# 1554E.net
KiCad netlist of a schematic drawn in EAGLE
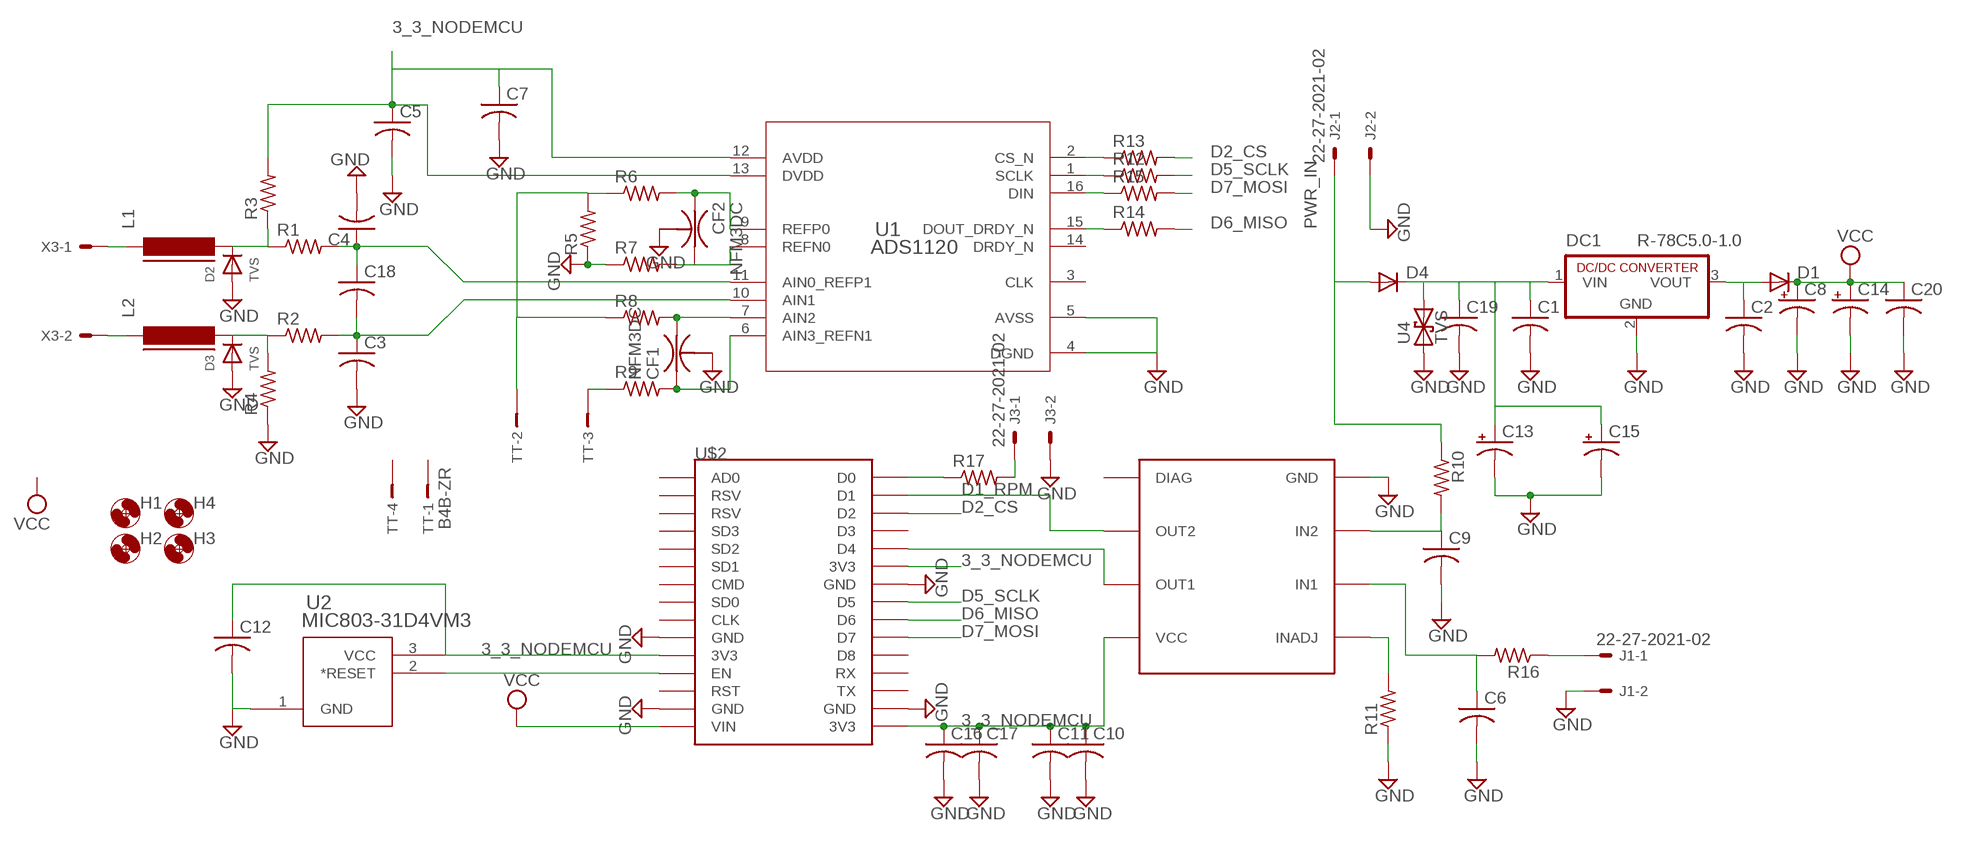
[diagram p0: schematic, sheet 1]

(export (version "E")
  (design (tool "Eeschema 10.0.6"))
  (components
    (comp (ref "C1")
      (value "C-USC0805K")
      (footprint "eagle-import:C0805K")
      (libsource (lib "eagle-import") (part "C-USC0805K"))
    )
    (comp (ref "C2")
      (value "C-USC0805K")
      (footprint "eagle-import:C0805K")
      (libsource (lib "eagle-import") (part "C-USC0805K"))
    )
    (comp (ref "C3")
      (value "C-USC0805K")
      (footprint "eagle-import:C0805K")
      (libsource (lib "eagle-import") (part "C-USC0805K"))
    )
    (comp (ref "C4")
      (value "C-USC0805K")
      (footprint "eagle-import:C0805K")
      (libsource (lib "eagle-import") (part "C-USC0805K"))
    )
    (comp (ref "C5")
      (value "C-USC0805K")
      (footprint "eagle-import:C0805K")
      (libsource (lib "eagle-import") (part "C-USC0805K"))
    )
    (comp (ref "C6")
      (value "C-USC0805K")
      (footprint "eagle-import:C0805K")
      (libsource (lib "eagle-import") (part "C-USC0805K"))
    )
    (comp (ref "C7")
      (value "C-USC0805K")
      (footprint "eagle-import:C0805K")
      (libsource (lib "eagle-import") (part "C-USC0805K"))
    )
    (comp (ref "C8")
      (value "CPOL-USE2.5-5")
      (footprint "eagle-import:E2,5-5")
      (libsource (lib "eagle-import") (part "CPOL-USE2.5-5"))
    )
    (comp (ref "C9")
      (value "C-USC0805K")
      (footprint "eagle-import:C0805K")
      (libsource (lib "eagle-import") (part "C-USC0805K"))
    )
    (comp (ref "C10")
      (value "C-USC0805K")
      (footprint "eagle-import:C0805K")
      (libsource (lib "eagle-import") (part "C-USC0805K"))
    )
    (comp (ref "C11")
      (value "C-USC0805K")
      (footprint "eagle-import:C0805K")
      (libsource (lib "eagle-import") (part "C-USC0805K"))
    )
    (comp (ref "C12")
      (value "C-USC0805K")
      (footprint "eagle-import:C0805K")
      (libsource (lib "eagle-import") (part "C-USC0805K"))
    )
    (comp (ref "C13")
      (value "CPOL-USE2.5-5")
      (footprint "eagle-import:E2,5-5")
      (libsource (lib "eagle-import") (part "CPOL-USE2.5-5"))
    )
    (comp (ref "C14")
      (value "CPOL-USE2.5-5")
      (footprint "eagle-import:E2,5-5")
      (libsource (lib "eagle-import") (part "CPOL-USE2.5-5"))
    )
    (comp (ref "C15")
      (value "CPOL-USE7.5-16")
      (footprint "eagle-import:E7,5-16")
      (libsource (lib "eagle-import") (part "CPOL-USE7.5-16"))
    )
    (comp (ref "C16")
      (value "C-USC1206K")
      (footprint "eagle-import:C1206K")
      (libsource (lib "eagle-import") (part "C-USC1206K"))
    )
    (comp (ref "C17")
      (value "C-USC1206K")
      (footprint "eagle-import:C1206K")
      (libsource (lib "eagle-import") (part "C-USC1206K"))
    )
    (comp (ref "C18")
      (value "C-USC0805K")
      (footprint "eagle-import:C0805K")
      (libsource (lib "eagle-import") (part "C-USC0805K"))
    )
    (comp (ref "C19")
      (value "C-USC1206K")
      (footprint "eagle-import:C1206K")
      (libsource (lib "eagle-import") (part "C-USC1206K"))
    )
    (comp (ref "C20")
      (value "C-USC1206K")
      (footprint "eagle-import:C1206K")
      (libsource (lib "eagle-import") (part "C-USC1206K"))
    )
    (comp (ref "CF1")
      (value "NFM3DC")
      (footprint "eagle-import:NFM3DC")
      (fields (field (name "MF") "FARNELL") (field (name "MPN") "NFM3DCC470U1H3L"))
      (libsource (lib "eagle-import") (part "NFM3DC"))
    )
    (comp (ref "CF2")
      (value "NFM3DC")
      (footprint "eagle-import:NFM3DC")
      (fields (field (name "MF") "FARNELL") (field (name "MPN") "NFM3DCC470U1H3L"))
      (libsource (lib "eagle-import") (part "NFM3DC"))
    )
    (comp (ref "D1")
      (value "DIODE-DO-214AC")
      (footprint "eagle-import:DO-214AC")
      (libsource (lib "eagle-import") (part "DIODE-DO-214AC"))
    )
    (comp (ref "D2")
      (value "TVS")
      (footprint "eagle-import:SOD-323F")
      (libsource (lib "eagle-import") (part "DIODESOD-323F"))
    )
    (comp (ref "D3")
      (value "TVS")
      (footprint "eagle-import:SOD-323F")
      (libsource (lib "eagle-import") (part "DIODESOD-323F"))
    )
    (comp (ref "D4")
      (value "DIODE-DO-214AC")
      (footprint "eagle-import:DO-214AC")
      (libsource (lib "eagle-import") (part "DIODE-DO-214AC"))
    )
    (comp (ref "DC1")
      (value "R-78C5.0-1.0")
      (footprint "eagle-import:SIP3")
      (libsource (lib "eagle-import") (part "R-78C-1.05.0"))
    )
    (comp (ref "H1")
      (value "MOUNT-HOLE2.8")
      (footprint "eagle-import:2,8")
      (libsource (lib "eagle-import") (part "MOUNT-HOLE2.8"))
    )
    (comp (ref "H2")
      (value "MOUNT-HOLE2.8")
      (footprint "eagle-import:2,8")
      (libsource (lib "eagle-import") (part "MOUNT-HOLE2.8"))
    )
    (comp (ref "H3")
      (value "MOUNT-HOLE2.8")
      (footprint "eagle-import:2,8")
      (libsource (lib "eagle-import") (part "MOUNT-HOLE2.8"))
    )
    (comp (ref "H4")
      (value "MOUNT-HOLE2.8")
      (footprint "eagle-import:2,8")
      (libsource (lib "eagle-import") (part "MOUNT-HOLE2.8"))
    )
    (comp (ref "J1")
      (value "22-27-2021-02")
      (footprint "eagle-import:6410-02")
      (libsource (lib "eagle-import") (part "22-?-0227-2021"))
    )
    (comp (ref "J2")
      (value "22-27-2021-02")
      (footprint "eagle-import:6410-02")
      (libsource (lib "eagle-import") (part "22-?-0227-2021"))
    )
    (comp (ref "J3")
      (value "22-27-2021-02")
      (footprint "eagle-import:6410-02")
      (libsource (lib "eagle-import") (part "22-?-0227-2021"))
    )
    (comp (ref "L1")
      (value "FERRITE-0805")
      (footprint "eagle-import:FB805")
      (libsource (lib "eagle-import") (part "FERRITE-0805"))
    )
    (comp (ref "L2")
      (value "FERRITE-0805")
      (footprint "eagle-import:FB805")
      (libsource (lib "eagle-import") (part "FERRITE-0805"))
    )
    (comp (ref "R1")
      (value "R-US_R0805W")
      (footprint "eagle-import:R0805W")
      (libsource (lib "eagle-import") (part "R-US_R0805W"))
    )
    (comp (ref "R2")
      (value "R-US_R0805W")
      (footprint "eagle-import:R0805W")
      (libsource (lib "eagle-import") (part "R-US_R0805W"))
    )
    (comp (ref "R3")
      (value "R-US_R0805W")
      (footprint "eagle-import:R0805W")
      (libsource (lib "eagle-import") (part "R-US_R0805W"))
    )
    (comp (ref "R4")
      (value "R-US_R0805W")
      (footprint "eagle-import:R0805W")
      (libsource (lib "eagle-import") (part "R-US_R0805W"))
    )
    (comp (ref "R5")
      (value "R-US_R0805W")
      (footprint "eagle-import:R0805W")
      (libsource (lib "eagle-import") (part "R-US_R0805W"))
    )
    (comp (ref "R6")
      (value "R-US_R0805W")
      (footprint "eagle-import:R0805W")
      (libsource (lib "eagle-import") (part "R-US_R0805W"))
    )
    (comp (ref "R7")
      (value "R-US_R0805W")
      (footprint "eagle-import:R0805W")
      (libsource (lib "eagle-import") (part "R-US_R0805W"))
    )
    (comp (ref "R8")
      (value "R-US_R0805W")
      (footprint "eagle-import:R0805W")
      (libsource (lib "eagle-import") (part "R-US_R0805W"))
    )
    (comp (ref "R9")
      (value "R-US_R0805W")
      (footprint "eagle-import:R0805W")
      (libsource (lib "eagle-import") (part "R-US_R0805W"))
    )
    (comp (ref "R10")
      (value "R-US_R0805W")
      (footprint "eagle-import:R0805W")
      (libsource (lib "eagle-import") (part "R-US_R0805W"))
    )
    (comp (ref "R11")
      (value "R-US_R0805W")
      (footprint "eagle-import:R0805W")
      (libsource (lib "eagle-import") (part "R-US_R0805W"))
    )
    (comp (ref "R12")
      (value "R-US_R0805W")
      (footprint "eagle-import:R0805W")
      (libsource (lib "eagle-import") (part "R-US_R0805W"))
    )
    (comp (ref "R13")
      (value "R-US_R0805W")
      (footprint "eagle-import:R0805W")
      (libsource (lib "eagle-import") (part "R-US_R0805W"))
    )
    (comp (ref "R14")
      (value "R-US_R0805W")
      (footprint "eagle-import:R0805W")
      (libsource (lib "eagle-import") (part "R-US_R0805W"))
    )
    (comp (ref "R15")
      (value "R-US_R0805W")
      (footprint "eagle-import:R0805W")
      (libsource (lib "eagle-import") (part "R-US_R0805W"))
    )
    (comp (ref "R16")
      (value "R-US_R0805W")
      (footprint "eagle-import:R0805W")
      (libsource (lib "eagle-import") (part "R-US_R0805W"))
    )
    (comp (ref "R17")
      (value "R-US_R0805W")
      (footprint "eagle-import:R0805W")
      (libsource (lib "eagle-import") (part "R-US_R0805W"))
    )
    (comp (ref "TT")
      (value "B4B-ZR")
      (footprint "eagle-import:B4B-ZR")
      (fields (field (name "MF") "FARNELL") (field (name "MPN") "B4B-ZR(LF)(SN)"))
      (libsource (lib "eagle-import") (part "?4B-ZRB"))
    )
    (comp (ref "U$1")
      (value "NCV1124")
      (footprint "eagle-import:TESTER")
      (libsource (lib "eagle-import") (part "NCV1124"))
    )
    (comp (ref "U$2")
      (value "ESP12E_DEVKIT")
      (footprint "eagle-import:ESP12E_DEVKIT")
      (libsource (lib "eagle-import") (part "ESP12E_DEVKIT"))
    )
    (comp (ref "U1")
      (value "ADS1120")
      (footprint "eagle-import:PW0016A_N")
      (fields
        (field (name "ALTERNATEPARTNUMBER") "ADS1120IPW")
        (field (name "MANUFACTURER") "Texas Instruments")
        (field (name "PARTNUMBER") "ADS1120IPWR")
      )
      (libsource (lib "eagle-import") (part "ADS1120IPWR"))
    )
    (comp (ref "U2")
      (value "MIC803-31D4VM3")
      (footprint "eagle-import:SOT-23_M3")
      (fields
        (field (name "MANUFACTURER_PART_NUMBER") "mic803-31d4vm3")
        (field (name "COPYRIGHT") "Copyright (C) 2015 Accelerated Designs. All rights reserved")
      )
      (libsource (lib "eagle-import") (part "MIC803-31D4VM3"))
    )
    (comp (ref "U4")
      (value "TVS")
      (footprint "eagle-import:SMA-DIODE")
      (libsource (lib "eagle-import") (part "TVS"))
    )
    (comp (ref "X3")
      (value "22-23-2021")
      (footprint "eagle-import:22-23-2021")
      (fields
        (field (name "MF") "MOLEX")
        (field (name "MF_1") "MOLEX")
        (field (name "MPN") "22-23-2021")
        (field (name "OC_FARNELL") "1462926")
        (field (name "OC_NEWARK") "25C3832")
      )
      (libsource (lib "eagle-import") (part "22-23-2021"))
    )
  )
  (nets
    (net (code "1") (name "/3_3_NODEMCU") (class "Default")
      (node (ref "C10") (pin "1") (pinfunction "1_1") (pintype "passive"))
      (node (ref "C11") (pin "1") (pinfunction "1_1") (pintype "passive"))
      (node (ref "C12") (pin "1") (pinfunction "1_1") (pintype "passive"))
      (node (ref "C16") (pin "1") (pinfunction "1_1") (pintype "passive"))
      (node (ref "C17") (pin "1") (pinfunction "1_1") (pintype "passive"))
      (node (ref "C5") (pin "1") (pinfunction "1_1") (pintype "passive"))
      (node (ref "C7") (pin "1") (pinfunction "1_1") (pintype "passive"))
      (node (ref "R3") (pin "2") (pinfunction "2_2") (pintype "passive"))
      (node (ref "U$1") (pin "VCC") (pinfunction "VCC_VCC") (pintype "bidirectional"))
      (node (ref "U$2") (pin "3V3@0") (pinfunction "3V3_3V3@0") (pintype "bidirectional"))
      (node (ref "U$2") (pin "3V3@1") (pinfunction "3V3_3V3@1") (pintype "bidirectional"))
      (node (ref "U$2") (pin "3V3@2") (pinfunction "3V3_3V3@2") (pintype "bidirectional"))
      (node (ref "U1") (pin "12") (pinfunction "AVDD_12") (pintype "power_in"))
      (node (ref "U1") (pin "13") (pinfunction "DVDD_13") (pintype "power_in"))
      (node (ref "U2") (pin "3") (pinfunction "VCC_3") (pintype "power_in"))
    )
    (net (code "2") (name "/D1_RPM") (class "Default")
      (node (ref "U$1") (pin "OUT2") (pinfunction "OUT2_OUT2") (pintype "bidirectional"))
      (node (ref "U$2") (pin "D1") (pinfunction "D1_D1") (pintype "bidirectional"))
    )
    (net (code "3") (name "/D2_CS") (class "Default")
      (node (ref "R13") (pin "2") (pinfunction "2_2") (pintype "passive"))
      (node (ref "U$2") (pin "D2") (pinfunction "D2_D2") (pintype "bidirectional"))
    )
    (net (code "4") (name "/D5_SCLK") (class "Default")
      (node (ref "R12") (pin "2") (pinfunction "2_2") (pintype "passive"))
      (node (ref "U$2") (pin "D5") (pinfunction "D5_D5") (pintype "bidirectional"))
    )
    (net (code "5") (name "/D6_MISO") (class "Default")
      (node (ref "R14") (pin "2") (pinfunction "2_2") (pintype "passive"))
      (node (ref "U$2") (pin "D6") (pinfunction "D6_D6") (pintype "bidirectional"))
    )
    (net (code "6") (name "/D7_MOSI") (class "Default")
      (node (ref "R15") (pin "2") (pinfunction "2_2") (pintype "passive"))
      (node (ref "U$2") (pin "D7") (pinfunction "D7_D7") (pintype "bidirectional"))
    )
    (net (code "7") (name "/PWR_IN") (class "Default")
      (node (ref "D4") (pin "A") (pinfunction "A_A") (pintype "passive"))
      (node (ref "J2") (pin "1") (pinfunction "S_1") (pintype "passive"))
      (node (ref "R10") (pin "1") (pinfunction "1_1") (pintype "passive"))
    )
    (net (code "8") (name "GND") (class "Default")
      (node (ref "C1") (pin "2") (pinfunction "2_2") (pintype "passive"))
      (node (ref "C10") (pin "2") (pinfunction "2_2") (pintype "passive"))
      (node (ref "C11") (pin "2") (pinfunction "2_2") (pintype "passive"))
      (node (ref "C12") (pin "2") (pinfunction "2_2") (pintype "passive"))
      (node (ref "C13") (pin "-") (pinfunction "-_-") (pintype "passive"))
      (node (ref "C14") (pin "-") (pinfunction "-_-") (pintype "passive"))
      (node (ref "C15") (pin "-") (pinfunction "-_-") (pintype "passive"))
      (node (ref "C16") (pin "2") (pinfunction "2_2") (pintype "passive"))
      (node (ref "C17") (pin "2") (pinfunction "2_2") (pintype "passive"))
      (node (ref "C19") (pin "2") (pinfunction "2_2") (pintype "passive"))
      (node (ref "C2") (pin "2") (pinfunction "2_2") (pintype "passive"))
      (node (ref "C20") (pin "2") (pinfunction "2_2") (pintype "passive"))
      (node (ref "C3") (pin "2") (pinfunction "2_2") (pintype "passive"))
      (node (ref "C4") (pin "2") (pinfunction "2_2") (pintype "passive"))
      (node (ref "C5") (pin "2") (pinfunction "2_2") (pintype "passive"))
      (node (ref "C6") (pin "2") (pinfunction "2_2") (pintype "passive"))
      (node (ref "C7") (pin "2") (pinfunction "2_2") (pintype "passive"))
      (node (ref "C8") (pin "-") (pinfunction "-_-") (pintype "passive"))
      (node (ref "C9") (pin "2") (pinfunction "2_2") (pintype "passive"))
      (node (ref "CF1") (pin "2@1") (pinfunction "2_2@1") (pintype "passive"))
      (node (ref "CF2") (pin "2@1") (pinfunction "2_2@1") (pintype "passive"))
      (node (ref "D2") (pin "A") (pinfunction "A_A") (pintype "passive"))
      (node (ref "D3") (pin "A") (pinfunction "A_A") (pintype "passive"))
      (node (ref "DC1") (pin "2") (pinfunction "GND_2") (pintype "passive"))
      (node (ref "J1") (pin "2") (pinfunction "S_2") (pintype "passive"))
      (node (ref "J2") (pin "2") (pinfunction "S_2") (pintype "passive"))
      (node (ref "J3") (pin "2") (pinfunction "S_2") (pintype "passive"))
      (node (ref "R11") (pin "1") (pinfunction "1_1") (pintype "passive"))
      (node (ref "R4") (pin "1") (pinfunction "1_1") (pintype "passive"))
      (node (ref "R5") (pin "1") (pinfunction "1_1") (pintype "passive"))
      (node (ref "R7") (pin "1") (pinfunction "1_1") (pintype "passive"))
      (node (ref "U$1") (pin "GND") (pinfunction "GND_GND") (pintype "bidirectional"))
      (node (ref "U$2") (pin "GND@0") (pinfunction "GND_GND@0") (pintype "bidirectional"))
      (node (ref "U$2") (pin "GND@1") (pinfunction "GND_GND@1") (pintype "bidirectional"))
      (node (ref "U$2") (pin "GND@2") (pinfunction "GND_GND@2") (pintype "bidirectional"))
      (node (ref "U$2") (pin "GND@3") (pinfunction "GND_GND@3") (pintype "bidirectional"))
      (node (ref "U1") (pin "4") (pinfunction "DGND_4") (pintype "power_in"))
      (node (ref "U1") (pin "5") (pinfunction "AVSS_5") (pintype "power_in"))
      (node (ref "U2") (pin "1") (pinfunction "GND_1") (pintype "power_in"))
      (node (ref "U4") (pin "A") (pinfunction "1_A") (pintype "passive"))
    )
    (net (code "9") (name "Net-(C6-Pad1)") (class "Default")
      (node (ref "C6") (pin "1") (pinfunction "1_1") (pintype "passive"))
      (node (ref "R16") (pin "2") (pinfunction "2_2") (pintype "passive"))
      (node (ref "U$1") (pin "IN1") (pinfunction "IN1_IN1") (pintype "bidirectional"))
    )
    (net (code "10") (name "Net-(C9-Pad1)") (class "Default")
      (node (ref "C9") (pin "1") (pinfunction "1_1") (pintype "passive"))
      (node (ref "R10") (pin "2") (pinfunction "2_2") (pintype "passive"))
      (node (ref "U$1") (pin "IN2") (pinfunction "IN2_IN2") (pintype "bidirectional"))
    )
    (net (code "11") (name "Net-(D2-PadC)") (class "Default")
      (node (ref "D2") (pin "C") (pinfunction "C_C") (pintype "passive"))
      (node (ref "L1") (pin "2") (pinfunction "2_2") (pintype "passive"))
      (node (ref "R1") (pin "1") (pinfunction "1_1") (pintype "passive"))
      (node (ref "R3") (pin "1") (pinfunction "1_1") (pintype "passive"))
    )
    (net (code "12") (name "Net-(D3-PadC)") (class "Default")
      (node (ref "D3") (pin "C") (pinfunction "C_C") (pintype "passive"))
      (node (ref "L2") (pin "2") (pinfunction "2_2") (pintype "passive"))
      (node (ref "R2") (pin "1") (pinfunction "1_1") (pintype "passive"))
      (node (ref "R4") (pin "2") (pinfunction "2_2") (pintype "passive"))
    )
    (net (code "13") (name "Net-(DC1-VIN)") (class "Default")
      (node (ref "C1") (pin "1") (pinfunction "1_1") (pintype "passive"))
      (node (ref "C13") (pin "+") (pinfunction "+_+") (pintype "passive"))
      (node (ref "C15") (pin "+") (pinfunction "+_+") (pintype "passive"))
      (node (ref "C19") (pin "1") (pinfunction "1_1") (pintype "passive"))
      (node (ref "D4") (pin "C") (pinfunction "C_C") (pintype "passive"))
      (node (ref "DC1") (pin "1") (pinfunction "VIN_1") (pintype "passive"))
      (node (ref "U4") (pin "C") (pinfunction "2_C") (pintype "passive"))
    )
    (net (code "14") (name "Net-(DC1-VOUT)") (class "Default")
      (node (ref "C2") (pin "1") (pinfunction "1_1") (pintype "passive"))
      (node (ref "D1") (pin "A") (pinfunction "A_A") (pintype "passive"))
      (node (ref "DC1") (pin "3") (pinfunction "VOUT_3") (pintype "passive"))
    )
    (net (code "15") (name "Net-(J1A-S)") (class "Default")
      (node (ref "J1") (pin "1") (pinfunction "S_1") (pintype "passive"))
      (node (ref "R16") (pin "1") (pinfunction "1_1") (pintype "passive"))
    )
    (net (code "16") (name "Net-(J3A-S)") (class "Default")
      (node (ref "J3") (pin "1") (pinfunction "S_1") (pintype "passive"))
      (node (ref "R17") (pin "2") (pinfunction "2_2") (pintype "passive"))
    )
    (net (code "17") (name "Net-(R11-Pad2)") (class "Default")
      (node (ref "R11") (pin "2") (pinfunction "2_2") (pintype "passive"))
      (node (ref "U$1") (pin "INADJ") (pinfunction "INADJ_INADJ") (pintype "bidirectional"))
    )
    (net (code "18") (name "Net-(R17-Pad1)") (class "Default")
      (node (ref "R17") (pin "1") (pinfunction "1_1") (pintype "passive"))
      (node (ref "U$2") (pin "D0") (pinfunction "D0_D0") (pintype "bidirectional"))
    )
    (net (code "19") (name "Net-(TTB-1)") (class "Default")
      (node (ref "R5") (pin "2") (pinfunction "2_2") (pintype "passive"))
      (node (ref "R6") (pin "1") (pinfunction "1_1") (pintype "passive"))
      (node (ref "R8") (pin "1") (pinfunction "1_1") (pintype "passive"))
      (node (ref "TT") (pin "2") (pinfunction "1_2") (pintype "passive"))
    )
    (net (code "20") (name "Net-(TTC-1)") (class "Default")
      (node (ref "R9") (pin "1") (pinfunction "1_1") (pintype "passive"))
      (node (ref "TT") (pin "3") (pinfunction "1_3") (pintype "passive"))
    )
    (net (code "21") (name "Net-(U$1-PadOUT1)") (class "Default")
      (node (ref "U$1") (pin "OUT1") (pinfunction "OUT1_OUT1") (pintype "bidirectional"))
      (node (ref "U$2") (pin "D4") (pinfunction "D4_D4") (pintype "bidirectional"))
    )
    (net (code "22") (name "Net-(U1-AIN0_REFP1)") (class "Default")
      (node (ref "C18") (pin "1") (pinfunction "1_1") (pintype "passive"))
      (node (ref "C4") (pin "1") (pinfunction "1_1") (pintype "passive"))
      (node (ref "R1") (pin "2") (pinfunction "2_2") (pintype "passive"))
      (node (ref "U1") (pin "11") (pinfunction "AIN0_REFP1_11") (pintype "input"))
    )
    (net (code "23") (name "Net-(U1-AIN1)") (class "Default")
      (node (ref "C18") (pin "2") (pinfunction "2_2") (pintype "passive"))
      (node (ref "C3") (pin "1") (pinfunction "1_1") (pintype "passive"))
      (node (ref "R2") (pin "2") (pinfunction "2_2") (pintype "passive"))
      (node (ref "U1") (pin "10") (pinfunction "AIN1_10") (pintype "input"))
    )
    (net (code "24") (name "Net-(U1-AIN2)") (class "Default")
      (node (ref "CF1") (pin "3") (pinfunction "3_3") (pintype "passive"))
      (node (ref "R8") (pin "2") (pinfunction "2_2") (pintype "passive"))
      (node (ref "U1") (pin "7") (pinfunction "AIN2_7") (pintype "input"))
    )
    (net (code "25") (name "Net-(U1-AIN3_REFN1)") (class "Default")
      (node (ref "CF1") (pin "1") (pinfunction "1_1") (pintype "passive"))
      (node (ref "R9") (pin "2") (pinfunction "2_2") (pintype "passive"))
      (node (ref "U1") (pin "6") (pinfunction "AIN3_REFN1_6") (pintype "input"))
    )
    (net (code "26") (name "Net-(U1-CS_N)") (class "Default")
      (node (ref "R13") (pin "1") (pinfunction "1_1") (pintype "passive"))
      (node (ref "U1") (pin "2") (pinfunction "CS_N_2") (pintype "input"))
    )
    (net (code "27") (name "Net-(U1-DIN)") (class "Default")
      (node (ref "R15") (pin "1") (pinfunction "1_1") (pintype "passive"))
      (node (ref "U1") (pin "16") (pinfunction "DIN_16") (pintype "input"))
    )
    (net (code "28") (name "Net-(U1-DOUT_DRDY_N)") (class "Default")
      (node (ref "R14") (pin "1") (pinfunction "1_1") (pintype "passive"))
      (node (ref "U1") (pin "15") (pinfunction "DOUT_DRDY_N_15") (pintype "output"))
    )
    (net (code "29") (name "Net-(U1-REFN0)") (class "Default")
      (node (ref "CF2") (pin "3") (pinfunction "3_3") (pintype "passive"))
      (node (ref "R7") (pin "2") (pinfunction "2_2") (pintype "passive"))
      (node (ref "U1") (pin "8") (pinfunction "REFN0_8") (pintype "input"))
    )
    (net (code "30") (name "Net-(U1-REFP0)") (class "Default")
      (node (ref "CF2") (pin "1") (pinfunction "1_1") (pintype "passive"))
      (node (ref "R6") (pin "2") (pinfunction "2_2") (pintype "passive"))
      (node (ref "U1") (pin "9") (pinfunction "REFP0_9") (pintype "input"))
    )
    (net (code "31") (name "Net-(U1-SCLK)") (class "Default")
      (node (ref "R12") (pin "1") (pinfunction "1_1") (pintype "passive"))
      (node (ref "U1") (pin "1") (pinfunction "SCLK_1") (pintype "input"))
    )
    (net (code "32") (name "Net-(U2-*RESET)") (class "Default")
      (node (ref "U$2") (pin "EN") (pinfunction "EN_EN") (pintype "bidirectional"))
      (node (ref "U2") (pin "2") (pinfunction "*RESET_2") (pintype "passive"))
    )
    (net (code "33") (name "Net-(X3A-S)") (class "Default")
      (node (ref "L1") (pin "1") (pinfunction "1_1") (pintype "passive"))
      (node (ref "X3") (pin "1") (pinfunction "S_1") (pintype "passive"))
    )
    (net (code "34") (name "Net-(X3B-S)") (class "Default")
      (node (ref "L2") (pin "1") (pinfunction "1_1") (pintype "passive"))
      (node (ref "X3") (pin "2") (pinfunction "S_2") (pintype "passive"))
    )
    (net (code "35") (name "VCC") (class "Default")
      (node (ref "C14") (pin "+") (pinfunction "+_+") (pintype "passive"))
      (node (ref "C20") (pin "1") (pinfunction "1_1") (pintype "passive"))
      (node (ref "C8") (pin "+") (pinfunction "+_+") (pintype "passive"))
      (node (ref "D1") (pin "C") (pinfunction "C_C") (pintype "passive"))
      (node (ref "U$2") (pin "VIN") (pinfunction "VIN_VIN") (pintype "bidirectional"))
    )
    (net (code "36") (name "unconnected-(CF1-2-Pad2@2)") (class "Default")
      (node (ref "CF1") (pin "2@2") (pinfunction "2_2@2") (pintype "passive"))
    )
    (net (code "37") (name "unconnected-(CF2-2-Pad2@2)") (class "Default")
      (node (ref "CF2") (pin "2@2") (pinfunction "2_2@2") (pintype "passive"))
    )
    (net (code "38") (name "unconnected-(TT-Pad1)") (class "Default")
      (node (ref "TT") (pin "1") (pinfunction "1_1") (pintype "passive"))
    )
    (net (code "39") (name "unconnected-(TTD-1-Pad4)") (class "Default")
      (node (ref "TT") (pin "4") (pinfunction "1_4") (pintype "passive"))
    )
    (net (code "40") (name "unconnected-(U$1-PadDIAG)") (class "Default")
      (node (ref "U$1") (pin "DIAG") (pinfunction "DIAG_DIAG") (pintype "bidirectional"))
    )
    (net (code "41") (name "unconnected-(U$2-PadAD0)") (class "Default")
      (node (ref "U$2") (pin "AD0") (pinfunction "AD0_AD0") (pintype "bidirectional"))
    )
    (net (code "42") (name "unconnected-(U$2-PadCLK)") (class "Default")
      (node (ref "U$2") (pin "CLK") (pinfunction "CLK_CLK") (pintype "bidirectional"))
    )
    (net (code "43") (name "unconnected-(U$2-PadCMD)") (class "Default")
      (node (ref "U$2") (pin "CMD") (pinfunction "CMD_CMD") (pintype "bidirectional"))
    )
    (net (code "44") (name "unconnected-(U$2-PadD3)") (class "Default")
      (node (ref "U$2") (pin "D3") (pinfunction "D3_D3") (pintype "bidirectional"))
    )
    (net (code "45") (name "unconnected-(U$2-PadD8)") (class "Default")
      (node (ref "U$2") (pin "D8") (pinfunction "D8_D8") (pintype "bidirectional"))
    )
    (net (code "46") (name "unconnected-(U$2-PadRST)") (class "Default")
      (node (ref "U$2") (pin "RST") (pinfunction "RST_RST") (pintype "bidirectional"))
    )
    (net (code "47") (name "unconnected-(U$2-PadRX)") (class "Default")
      (node (ref "U$2") (pin "RX") (pinfunction "RX_RX") (pintype "bidirectional"))
    )
    (net (code "48") (name "unconnected-(U$2-PadSD0)") (class "Default")
      (node (ref "U$2") (pin "SD0") (pinfunction "SD0_SD0") (pintype "bidirectional"))
    )
    (net (code "49") (name "unconnected-(U$2-PadSD1)") (class "Default")
      (node (ref "U$2") (pin "SD1") (pinfunction "SD1_SD1") (pintype "bidirectional"))
    )
    (net (code "50") (name "unconnected-(U$2-PadSD2)") (class "Default")
      (node (ref "U$2") (pin "SD2") (pinfunction "SD2_SD2") (pintype "bidirectional"))
    )
    (net (code "51") (name "unconnected-(U$2-PadSD3)") (class "Default")
      (node (ref "U$2") (pin "SD3") (pinfunction "SD3_SD3") (pintype "bidirectional"))
    )
    (net (code "52") (name "unconnected-(U$2-PadTX)") (class "Default")
      (node (ref "U$2") (pin "TX") (pinfunction "TX_TX") (pintype "bidirectional"))
    )
    (net (code "53") (name "unconnected-(U$2-RSV-PadRSV@0)") (class "Default")
      (node (ref "U$2") (pin "RSV@0") (pinfunction "RSV_RSV@0") (pintype "bidirectional"))
    )
    (net (code "54") (name "unconnected-(U$2-RSV-PadRSV@1)") (class "Default")
      (node (ref "U$2") (pin "RSV@1") (pinfunction "RSV_RSV@1") (pintype "bidirectional"))
    )
    (net (code "55") (name "unconnected-(U1-CLK-Pad3)") (class "Default")
      (node (ref "U1") (pin "3") (pinfunction "CLK_3") (pintype "input"))
    )
    (net (code "56") (name "unconnected-(U1-DRDY_N-Pad14)") (class "Default")
      (node (ref "U1") (pin "14") (pinfunction "DRDY_N_14") (pintype "output"))
    )
  )
)
